# PCB_control_glider_v21.net
KiCad netlist of a schematic drawn in EAGLE
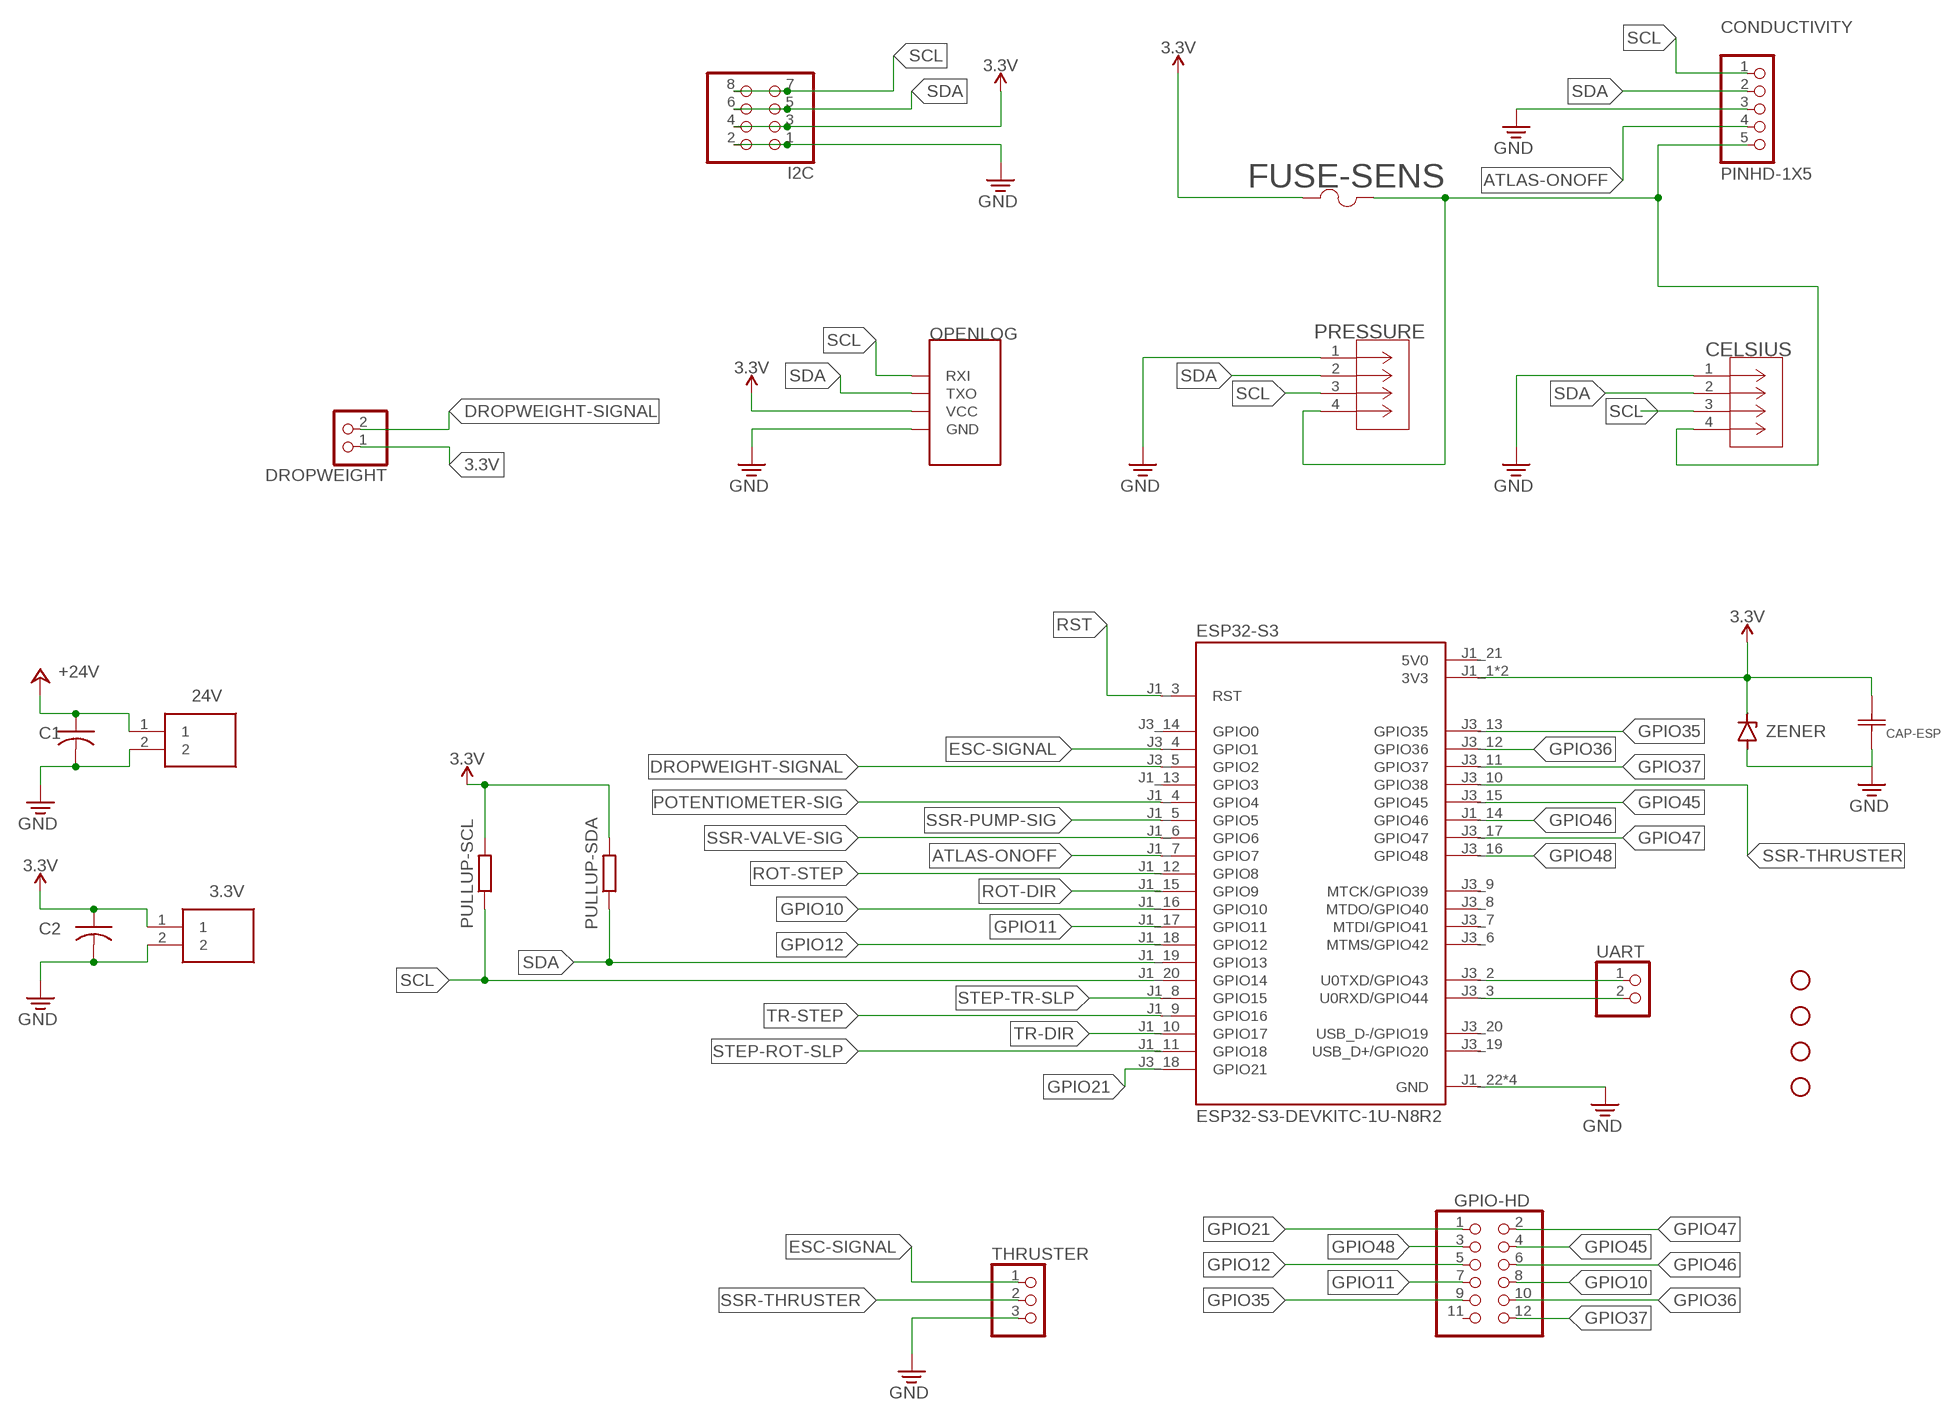
[diagram p0: schematic, sheet 1, part 1 of 2]
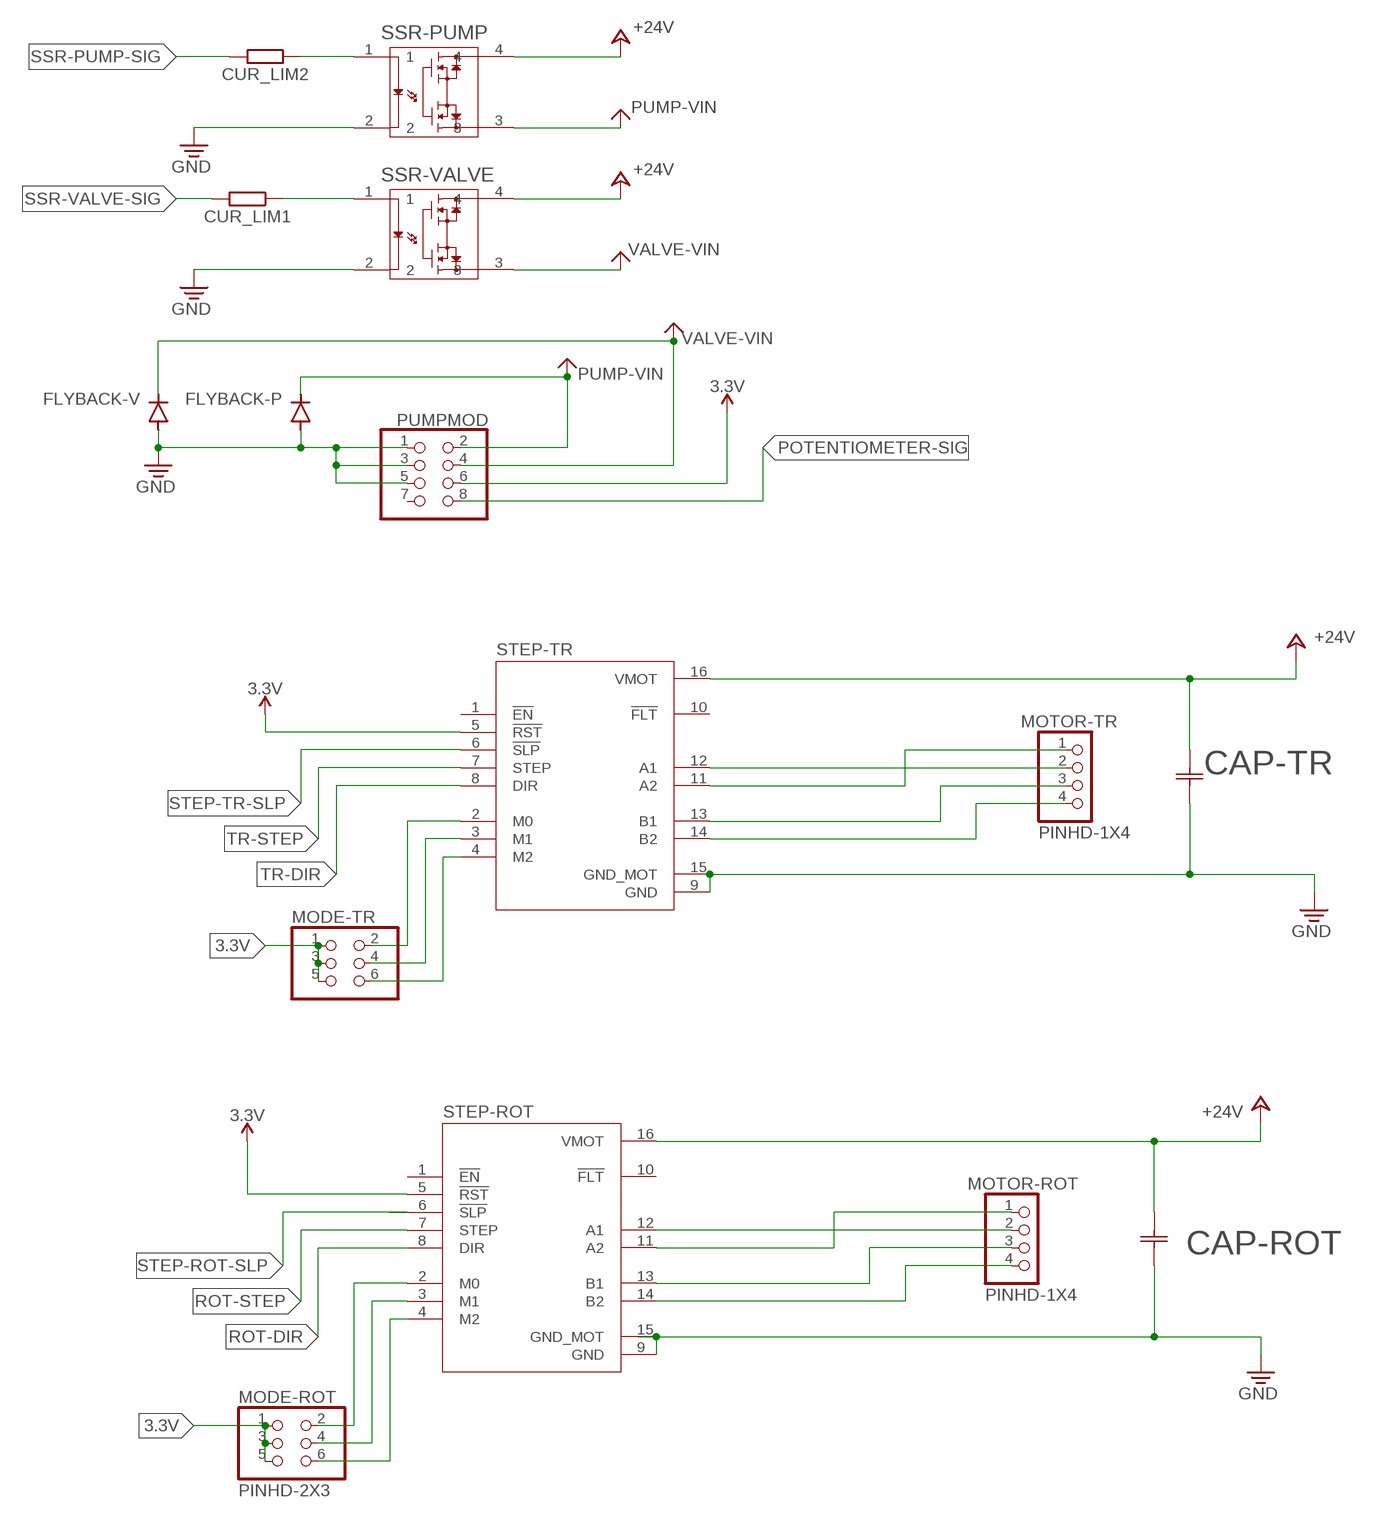
[diagram p1: schematic, sheet 1, part 2 of 2]

(export (version "E")
  (design (tool "Eeschema 10.0.6"))
  (components
    (comp (ref "3.3V")
      (value "CTBP0508_2")
      (footprint "eagle-import:CTBP05082")
      (fields (field (name "MANUFACTURER_PART_NUMBER") "CTBP0508/2"))
      (libsource (lib "eagle-import") (part "CTBP0508_2"))
    )
    (comp (ref "24V")
      (value "CTBP0508_2")
      (footprint "eagle-import:CTBP05082")
      (fields (field (name "MANUFACTURER_PART_NUMBER") "CTBP0508/2"))
      (libsource (lib "eagle-import") (part "CTBP0508_2"))
    )
    (comp (ref "C1")
      (value "ECA-1HM100")
      (footprint "eagle-import:CAP_RADIAL_2MM")
      (fields
        (field (name "DIGIKEY_PART_NUMBER") "P5178-ND")
        (field (name "MANUFACTURER") "Panasonic Electronic Components")
        (field (name "CREATED_BY") "PCBLayout.com")
      )
      (libsource (lib "eagle-import") (part "ECA-1HM100"))
    )
    (comp (ref "C2")
      (value "ECA-1HM100")
      (footprint "eagle-import:CAP_RADIAL_2MM")
      (fields
        (field (name "DIGIKEY_PART_NUMBER") "P5178-ND")
        (field (name "MANUFACTURER") "Panasonic Electronic Components")
        (field (name "CREATED_BY") "PCBLayout.com")
      )
      (libsource (lib "eagle-import") (part "ECA-1HM100"))
    )
    (comp (ref "CAP-ESP")
      (value "EEUHD1H101BCAP_PAN_8X11.5_PAN")
      (footprint "eagle-import:CAP_PAN_8X11.5_PAN")
      (fields
        (field (name "MANUFACTURER_PART_NUMBER") "EEUHD1H101B")
        (field (name "COPYRIGHT") "Copyright (C) 2024 Ultra Librarian. All rights reserved.")
      )
      (libsource (lib "eagle-import") (part "EEUHD1H101BCAP_PAN_8X11.5_PAN"))
    )
    (comp (ref "CAP-ROT")
      (value "EEUHD1H101BCAP_PAN_8X11.5_PAN")
      (footprint "eagle-import:CAP_PAN_8X11.5_PAN")
      (fields
        (field (name "MANUFACTURER_PART_NUMBER") "EEUHD1H101B")
        (field (name "COPYRIGHT") "Copyright (C) 2024 Ultra Librarian. All rights reserved.")
      )
      (libsource (lib "eagle-import") (part "EEUHD1H101BCAP_PAN_8X11.5_PAN"))
    )
    (comp (ref "CAP-TR")
      (value "EEUHD1H101BCAP_PAN_8X11.5_PAN")
      (footprint "eagle-import:CAP_PAN_8X11.5_PAN")
      (fields
        (field (name "MANUFACTURER_PART_NUMBER") "EEUHD1H101B")
        (field (name "COPYRIGHT") "Copyright (C) 2024 Ultra Librarian. All rights reserved.")
      )
      (libsource (lib "eagle-import") (part "EEUHD1H101BCAP_PAN_8X11.5_PAN"))
    )
    (comp (ref "CELSIUS")
      (value "BM04B-GHS-TBTCONN_BM04B-GHS-TBT_JST")
      (footprint "eagle-import:CONN_BM04B-GHS-TBT_JST")
      (fields
        (field (name "MANUFACTURER_PART_NUMBER") "BM04B-GHS-TBT")
        (field (name "COPYRIGHT") "Copyright (C) 2024 Ultra Librarian. All rights reserved.")
      )
      (libsource (lib "eagle-import") (part "BM04B-GHS-TBTCONN_BM04B-GHS-TBT_JST"))
    )
    (comp (ref "CONDUCTIVITY")
      (value "PINHD-1X5")
      (footprint "eagle-import:1X05")
      (fields (field (name "MANUFACTURER") "Generic"))
      (libsource (lib "eagle-import") (part "PINHD-1X5"))
    )
    (comp (ref "CUR_LIM1")
      (value "RESISTOR-BACKUP_AXIAL-10.16MM-PITCH")
      (footprint "eagle-import:RESAD1016W63L850D250B")
      (libsource (lib "eagle-import") (part "RESISTOR-BACKUP_AXIAL-10.16MM-PITCH"))
    )
    (comp (ref "CUR_LIM2")
      (value "RESISTOR-BACKUP_AXIAL-10.16MM-PITCH")
      (footprint "eagle-import:RESAD1016W63L850D250B")
      (libsource (lib "eagle-import") (part "RESISTOR-BACKUP_AXIAL-10.16MM-PITCH"))
    )
    (comp (ref "DROPWEIGHT")
      (value "PINHD-1X2")
      (footprint "eagle-import:1X02")
      (libsource (lib "eagle-import") (part "PINHD-1X2"))
    )
    (comp (ref "ESP32-S3")
      (value "ESP32-S3-DEVKITC-1U-N8R2")
      (footprint "eagle-import:XCVR_ESP32-S3-DEVKITC-1U-N8R2")
      (fields (field (name "MF") "Espressif Systems"))
      (libsource (lib "eagle-import") (part "ESP32-S3-DEVKITC-1U-N8R2"))
    )
    (comp (ref "FLYBACK-P")
      (value "1N4004")
      (footprint "eagle-import:DO-41")
      (fields
        (field (name "DIGIKEY_PART_NUMBER") "1N4004MSCT-ND")
        (field (name "MANUFACTURER") "Micro Commercial Co")
        (field (name "CREATED_BY") "PCBLayout.com")
      )
      (libsource (lib "eagle-import") (part "1N4004"))
    )
    (comp (ref "FLYBACK-V")
      (value "1N4004")
      (footprint "eagle-import:DO-41")
      (fields
        (field (name "DIGIKEY_PART_NUMBER") "1N4004MSCT-ND")
        (field (name "MANUFACTURER") "Micro Commercial Co")
        (field (name "CREATED_BY") "PCBLayout.com")
      )
      (libsource (lib "eagle-import") (part "1N4004"))
    )
    (comp (ref "FUSE-SENS")
      (value "LVR033KFUS_LVR033_TYCO_TYC")
      (footprint "eagle-import:FUS_LVR033_TYCO_TYC")
      (fields
        (field (name "MANUFACTURER_PART_NUMBER") "LVR033K")
        (field (name "COPYRIGHT") "Copyright (C) 2024 Ultra Librarian. All rights reserved.")
      )
      (libsource (lib "eagle-import") (part "LVR033KFUS_LVR033_TYCO_TYC"))
    )
    (comp (ref "GPIO-HD")
      (value "PINHD-2X6")
      (footprint "eagle-import:2X06")
      (fields (field (name "MANUFACTURER") "Generic"))
      (libsource (lib "eagle-import") (part "PINHD-2X6"))
    )
    (comp (ref "H1")
      (value "STAND-OFFTIGHT")
      (footprint "eagle-import:STAND-OFF-TIGHT")
      (libsource (lib "eagle-import") (part "STAND-OFFTIGHT"))
    )
    (comp (ref "H2")
      (value "STAND-OFFTIGHT")
      (footprint "eagle-import:STAND-OFF-TIGHT")
      (libsource (lib "eagle-import") (part "STAND-OFFTIGHT"))
    )
    (comp (ref "H3")
      (value "STAND-OFFTIGHT")
      (footprint "eagle-import:STAND-OFF-TIGHT")
      (libsource (lib "eagle-import") (part "STAND-OFFTIGHT"))
    )
    (comp (ref "H4")
      (value "STAND-OFFTIGHT")
      (footprint "eagle-import:STAND-OFF-TIGHT")
      (libsource (lib "eagle-import") (part "STAND-OFFTIGHT"))
    )
    (comp (ref "I2C")
      (value "PINHD-2X4")
      (footprint "eagle-import:2X04")
      (libsource (lib "eagle-import") (part "PINHD-2X4"))
    )
    (comp (ref "MODE-ROT")
      (value "PINHD-2X3")
      (footprint "eagle-import:2X03")
      (fields (field (name "MANUFACTURER") "Generic"))
      (libsource (lib "eagle-import") (part "PINHD-2X3"))
    )
    (comp (ref "MODE-TR")
      (value "PINHD-2X3")
      (footprint "eagle-import:2X03")
      (fields (field (name "MANUFACTURER") "Generic"))
      (libsource (lib "eagle-import") (part "PINHD-2X3"))
    )
    (comp (ref "MOTOR-ROT")
      (value "PINHD-1X4")
      (footprint "eagle-import:1X04")
      (fields (field (name "MANUFACTURER") "Generic"))
      (libsource (lib "eagle-import") (part "PINHD-1X4"))
    )
    (comp (ref "MOTOR-TR")
      (value "PINHD-1X4")
      (footprint "eagle-import:1X04")
      (fields (field (name "MANUFACTURER") "Generic"))
      (libsource (lib "eagle-import") (part "PINHD-1X4"))
    )
    (comp (ref "PRESSURE")
      (value "BM04B-GHS-TBTCONN_BM04B-GHS-TBT_JST")
      (footprint "eagle-import:CONN_BM04B-GHS-TBT_JST")
      (fields
        (field (name "MANUFACTURER_PART_NUMBER") "BM04B-GHS-TBT")
        (field (name "COPYRIGHT") "Copyright (C) 2024 Ultra Librarian. All rights reserved.")
      )
      (libsource (lib "eagle-import") (part "BM04B-GHS-TBTCONN_BM04B-GHS-TBT_JST"))
    )
    (comp (ref "PULLUP-SCL")
      (value "RESISTOR-BACKUP_AXIAL-10.16MM-PITCH")
      (footprint "eagle-import:RESAD1016W63L850D250B")
      (libsource (lib "eagle-import") (part "RESISTOR-BACKUP_AXIAL-10.16MM-PITCH"))
    )
    (comp (ref "PULLUP-SDA")
      (value "RESISTOR-BACKUP_AXIAL-10.16MM-PITCH")
      (footprint "eagle-import:RESAD1016W63L850D250B")
      (libsource (lib "eagle-import") (part "RESISTOR-BACKUP_AXIAL-10.16MM-PITCH"))
    )
    (comp (ref "PUMPMOD")
      (value "PINHD-2X4")
      (footprint "eagle-import:2X04")
      (libsource (lib "eagle-import") (part "PINHD-2X4"))
    )
    (comp (ref "QWIIC-OPENLOG")
      (value "OPENLOG")
      (footprint "eagle-import:OPENLOG")
      (libsource (lib "eagle-import") (part "OPENLOG"))
    )
    (comp (ref "SSR-PUMP")
      (value "G3VM-61ARA-DIP4_THD_OMR")
      (footprint "eagle-import:A-DIP4_THD_OMR")
      (fields
        (field (name "MANUFACTURER_PART_NUMBER") "G3VM-61AR")
        (field (name "COPYRIGHT") "Copyright (C) 2024 Ultra Librarian. All rights reserved.")
      )
      (libsource (lib "eagle-import") (part "G3VM-61ARA-DIP4_THD_OMR"))
    )
    (comp (ref "SSR-VALVE")
      (value "G3VM-61ARA-DIP4_THD_OMR")
      (footprint "eagle-import:A-DIP4_THD_OMR")
      (fields
        (field (name "MANUFACTURER_PART_NUMBER") "G3VM-61AR")
        (field (name "COPYRIGHT") "Copyright (C) 2024 Ultra Librarian. All rights reserved.")
      )
      (libsource (lib "eagle-import") (part "G3VM-61ARA-DIP4_THD_OMR"))
    )
    (comp (ref "STEP-ROT")
      (value "DRV8825_STEPPER_MOTOR_DRIVER_CARRIER")
      (footprint "eagle-import:IC_DRV8825_STEPPER_MOTOR_DRIVER_CARRIER")
      (fields (field (name "MF") "Pololu") (field (name "MP") "DRV8825 STEPPER MOTOR DRIVER CARRIER"))
      (libsource (lib "eagle-import") (part "DRV8825_STEPPER_MOTOR_DRIVER_CARRIER"))
    )
    (comp (ref "STEP-TR")
      (value "DRV8825_STEPPER_MOTOR_DRIVER_CARRIER")
      (footprint "eagle-import:IC_DRV8825_STEPPER_MOTOR_DRIVER_CARRIER")
      (fields (field (name "MF") "Pololu") (field (name "MP") "DRV8825 STEPPER MOTOR DRIVER CARRIER"))
      (libsource (lib "eagle-import") (part "DRV8825_STEPPER_MOTOR_DRIVER_CARRIER"))
    )
    (comp (ref "THRUSTER")
      (value "PINHD-1X3")
      (footprint "eagle-import:1X03")
      (libsource (lib "eagle-import") (part "PINHD-1X3"))
    )
    (comp (ref "UART")
      (value "PINHD-1X2")
      (footprint "eagle-import:1X02")
      (libsource (lib "eagle-import") (part "PINHD-1X2"))
    )
    (comp (ref "ZENER")
      (value "ZENER_DIODE-AXIAL")
      (footprint "eagle-import:DIODE-AXIAL")
      (libsource (lib "eagle-import") (part "ZENER_DIODE-AXIAL"))
    )
  )
  (nets
    (net (code "1") (name "+24V") (class "Default")
      (node (ref "24V") (pin "1") (pinfunction "1_1") (pintype "bidirectional"))
      (node (ref "C1") (pin "1") (pinfunction "1_1") (pintype "passive"))
      (node (ref "CAP-ROT") (pin "1") (pinfunction "1_1") (pintype "passive"))
      (node (ref "CAP-TR") (pin "1") (pinfunction "1_1") (pintype "passive"))
      (node (ref "SSR-PUMP") (pin "4") (pinfunction "4_4") (pintype "passive"))
      (node (ref "SSR-VALVE") (pin "4") (pinfunction "4_4") (pintype "passive"))
      (node (ref "STEP-ROT") (pin "16") (pinfunction "VMOT_16") (pintype "power_in"))
      (node (ref "STEP-TR") (pin "16") (pinfunction "VMOT_16") (pintype "power_in"))
    )
    (net (code "2") (name "/5V0") (class "Default")
      (node (ref "ESP32-S3") (pin "J1_21") (pinfunction "5V0_J1_21") (pintype "power_in"))
    )
    (net (code "3") (name "3.3V") (class "Default")
      (node (ref "3.3V") (pin "1") (pinfunction "1_1") (pintype "bidirectional"))
      (node (ref "C2") (pin "1") (pinfunction "1_1") (pintype "passive"))
      (node (ref "CAP-ESP") (pin "1") (pinfunction "1_1") (pintype "passive"))
      (node (ref "DROPWEIGHT") (pin "1") (pinfunction "1_1") (pintype "passive"))
      (node (ref "ESP32-S3") (pin "J1_1") (pinfunction "3V3_J1_1") (pintype "power_in"))
      (node (ref "ESP32-S3") (pin "J1_2") (pinfunction "3V3_J1_2") (pintype "power_in"))
      (node (ref "FUSE-SENS") (pin "1") (pinfunction "1_1") (pintype "passive"))
      (node (ref "I2C") (pin "3") (pinfunction "3_3") (pintype "passive"))
      (node (ref "I2C") (pin "4") (pinfunction "4_4") (pintype "passive"))
      (node (ref "MODE-ROT") (pin "1") (pinfunction "1_1") (pintype "passive"))
      (node (ref "MODE-ROT") (pin "3") (pinfunction "3_3") (pintype "passive"))
      (node (ref "MODE-ROT") (pin "5") (pinfunction "5_5") (pintype "passive"))
      (node (ref "MODE-TR") (pin "1") (pinfunction "1_1") (pintype "passive"))
      (node (ref "MODE-TR") (pin "3") (pinfunction "3_3") (pintype "passive"))
      (node (ref "MODE-TR") (pin "5") (pinfunction "5_5") (pintype "passive"))
      (node (ref "PULLUP-SCL") (pin "2") (pinfunction "2_2") (pintype "passive"))
      (node (ref "PULLUP-SDA") (pin "2") (pinfunction "2_2") (pintype "passive"))
      (node (ref "PUMPMOD") (pin "6") (pinfunction "6_6") (pintype "passive"))
      (node (ref "QWIIC-OPENLOG") (pin "VCC") (pinfunction "VCC_VCC") (pintype "power_in"))
      (node (ref "STEP-ROT") (pin "5") (pinfunction "~{RST}_5") (pintype "input"))
      (node (ref "STEP-TR") (pin "5") (pinfunction "~{RST}_5") (pintype "input"))
      (node (ref "ZENER") (pin "2") (pinfunction "C_2") (pintype "passive"))
    )
    (net (code "4") (name "ATLAS-ONOFF") (class "Default")
      (node (ref "CONDUCTIVITY") (pin "4") (pinfunction "4_4") (pintype "passive"))
      (node (ref "ESP32-S3") (pin "J1_7") (pinfunction "GPIO7_J1_7") (pintype "bidirectional"))
    )
    (net (code "5") (name "DROPWEIGHT-SIGNAL") (class "Default")
      (node (ref "DROPWEIGHT") (pin "2") (pinfunction "2_2") (pintype "passive"))
      (node (ref "ESP32-S3") (pin "J3_5") (pinfunction "GPIO2_J3_5") (pintype "bidirectional"))
    )
    (net (code "6") (name "ESC-SIGNAL") (class "Default")
      (node (ref "ESP32-S3") (pin "J3_4") (pinfunction "GPIO1_J3_4") (pintype "bidirectional"))
      (node (ref "THRUSTER") (pin "1") (pinfunction "1_1") (pintype "passive"))
    )
    (net (code "7") (name "GND") (class "Default")
      (node (ref "24V") (pin "2") (pinfunction "2_2") (pintype "bidirectional"))
      (node (ref "3.3V") (pin "2") (pinfunction "2_2") (pintype "bidirectional"))
      (node (ref "C1") (pin "2") (pinfunction "2_2") (pintype "passive"))
      (node (ref "C2") (pin "2") (pinfunction "2_2") (pintype "passive"))
      (node (ref "CAP-ESP") (pin "2") (pinfunction "2_2") (pintype "passive"))
      (node (ref "CAP-ROT") (pin "2") (pinfunction "2_2") (pintype "passive"))
      (node (ref "CAP-TR") (pin "2") (pinfunction "2_2") (pintype "passive"))
      (node (ref "CELSIUS") (pin "1") (pinfunction "1_1") (pintype "passive"))
      (node (ref "CONDUCTIVITY") (pin "3") (pinfunction "3_3") (pintype "passive"))
      (node (ref "ESP32-S3") (pin "J1_22") (pinfunction "GND_J1_22") (pintype "power_in"))
      (node (ref "ESP32-S3") (pin "J3_1") (pinfunction "GND_J3_1") (pintype "power_in"))
      (node (ref "ESP32-S3") (pin "J3_21") (pinfunction "GND_J3_21") (pintype "power_in"))
      (node (ref "ESP32-S3") (pin "J3_22") (pinfunction "GND_J3_22") (pintype "power_in"))
      (node (ref "FLYBACK-P") (pin "A") (pinfunction "A_A") (pintype "passive"))
      (node (ref "FLYBACK-V") (pin "A") (pinfunction "A_A") (pintype "passive"))
      (node (ref "I2C") (pin "1") (pinfunction "1_1") (pintype "passive"))
      (node (ref "I2C") (pin "2") (pinfunction "2_2") (pintype "passive"))
      (node (ref "PRESSURE") (pin "1") (pinfunction "1_1") (pintype "passive"))
      (node (ref "PUMPMOD") (pin "1") (pinfunction "1_1") (pintype "passive"))
      (node (ref "PUMPMOD") (pin "3") (pinfunction "3_3") (pintype "passive"))
      (node (ref "PUMPMOD") (pin "5") (pinfunction "5_5") (pintype "passive"))
      (node (ref "QWIIC-OPENLOG") (pin "GND") (pinfunction "GND_GND") (pintype "power_in"))
      (node (ref "SSR-PUMP") (pin "2") (pinfunction "2_2") (pintype "passive"))
      (node (ref "SSR-VALVE") (pin "2") (pinfunction "2_2") (pintype "passive"))
      (node (ref "STEP-ROT") (pin "15") (pinfunction "GND_MOT_15") (pintype "power_in"))
      (node (ref "STEP-ROT") (pin "9") (pinfunction "GND_9") (pintype "power_in"))
      (node (ref "STEP-TR") (pin "15") (pinfunction "GND_MOT_15") (pintype "power_in"))
      (node (ref "STEP-TR") (pin "9") (pinfunction "GND_9") (pintype "power_in"))
      (node (ref "THRUSTER") (pin "3") (pinfunction "3_3") (pintype "passive"))
      (node (ref "ZENER") (pin "1") (pinfunction "A_1") (pintype "passive"))
    )
    (net (code "8") (name "GPIO10") (class "Default")
      (node (ref "ESP32-S3") (pin "J1_16") (pinfunction "GPIO10_J1_16") (pintype "bidirectional"))
      (node (ref "GPIO-HD") (pin "8") (pinfunction "8_8") (pintype "passive"))
    )
    (net (code "9") (name "GPIO11") (class "Default")
      (node (ref "ESP32-S3") (pin "J1_17") (pinfunction "GPIO11_J1_17") (pintype "bidirectional"))
      (node (ref "GPIO-HD") (pin "7") (pinfunction "7_7") (pintype "passive"))
    )
    (net (code "10") (name "GPIO12") (class "Default")
      (node (ref "ESP32-S3") (pin "J1_18") (pinfunction "GPIO12_J1_18") (pintype "bidirectional"))
      (node (ref "GPIO-HD") (pin "5") (pinfunction "5_5") (pintype "passive"))
    )
    (net (code "11") (name "GPIO21") (class "Default")
      (node (ref "ESP32-S3") (pin "J3_18") (pinfunction "GPIO21_J3_18") (pintype "bidirectional"))
      (node (ref "GPIO-HD") (pin "1") (pinfunction "1_1") (pintype "passive"))
    )
    (net (code "12") (name "GPIO35") (class "Default")
      (node (ref "ESP32-S3") (pin "J3_13") (pinfunction "GPIO35_J3_13") (pintype "bidirectional"))
      (node (ref "GPIO-HD") (pin "9") (pinfunction "9_9") (pintype "passive"))
    )
    (net (code "13") (name "GPIO36") (class "Default")
      (node (ref "ESP32-S3") (pin "J3_12") (pinfunction "GPIO36_J3_12") (pintype "bidirectional"))
      (node (ref "GPIO-HD") (pin "10") (pinfunction "10_10") (pintype "passive"))
    )
    (net (code "14") (name "GPIO37") (class "Default")
      (node (ref "ESP32-S3") (pin "J3_11") (pinfunction "GPIO37_J3_11") (pintype "bidirectional"))
      (node (ref "GPIO-HD") (pin "12") (pinfunction "12_12") (pintype "passive"))
    )
    (net (code "15") (name "GPIO45") (class "Default")
      (node (ref "ESP32-S3") (pin "J3_15") (pinfunction "GPIO45_J3_15") (pintype "bidirectional"))
      (node (ref "GPIO-HD") (pin "4") (pinfunction "4_4") (pintype "passive"))
    )
    (net (code "16") (name "GPIO46") (class "Default")
      (node (ref "ESP32-S3") (pin "J1_14") (pinfunction "GPIO46_J1_14") (pintype "bidirectional"))
      (node (ref "GPIO-HD") (pin "6") (pinfunction "6_6") (pintype "passive"))
    )
    (net (code "17") (name "GPIO47") (class "Default")
      (node (ref "ESP32-S3") (pin "J3_17") (pinfunction "GPIO47_J3_17") (pintype "bidirectional"))
      (node (ref "GPIO-HD") (pin "2") (pinfunction "2_2") (pintype "passive"))
    )
    (net (code "18") (name "GPIO48") (class "Default")
      (node (ref "ESP32-S3") (pin "J3_16") (pinfunction "GPIO48_J3_16") (pintype "bidirectional"))
      (node (ref "GPIO-HD") (pin "3") (pinfunction "3_3") (pintype "passive"))
    )
    (net (code "19") (name "Net-(CELSIUS-Pad4)") (class "Default")
      (node (ref "CELSIUS") (pin "4") (pinfunction "4_4") (pintype "passive"))
      (node (ref "CONDUCTIVITY") (pin "5") (pinfunction "5_5") (pintype "passive"))
      (node (ref "FUSE-SENS") (pin "2") (pinfunction "2_2") (pintype "passive"))
      (node (ref "PRESSURE") (pin "4") (pinfunction "4_4") (pintype "passive"))
    )
    (net (code "20") (name "Net-(CUR_LIM1-Pad1)") (class "Default")
      (node (ref "CUR_LIM1") (pin "1") (pinfunction "1_1") (pintype "passive"))
      (node (ref "SSR-VALVE") (pin "1") (pinfunction "1_1") (pintype "passive"))
    )
    (net (code "21") (name "Net-(CUR_LIM2-Pad1)") (class "Default")
      (node (ref "CUR_LIM2") (pin "1") (pinfunction "1_1") (pintype "passive"))
      (node (ref "SSR-PUMP") (pin "1") (pinfunction "1_1") (pintype "passive"))
    )
    (net (code "22") (name "Net-(ESP32-S3-U0RXD{slash}GPIO44)") (class "Default")
      (node (ref "ESP32-S3") (pin "J3_3") (pinfunction "U0RXD/GPIO44_J3_3") (pintype "bidirectional"))
      (node (ref "UART") (pin "2") (pinfunction "2_2") (pintype "passive"))
    )
    (net (code "23") (name "Net-(ESP32-S3-U0TXD{slash}GPIO43)") (class "Default")
      (node (ref "ESP32-S3") (pin "J3_2") (pinfunction "U0TXD/GPIO43_J3_2") (pintype "bidirectional"))
      (node (ref "UART") (pin "1") (pinfunction "1_1") (pintype "passive"))
    )
    (net (code "24") (name "Net-(STEP-ROT-A1)") (class "Default")
      (node (ref "MOTOR-ROT") (pin "2") (pinfunction "2_2") (pintype "passive"))
      (node (ref "STEP-ROT") (pin "12") (pinfunction "A1_12") (pintype "output"))
    )
    (net (code "25") (name "Net-(STEP-ROT-A2)") (class "Default")
      (node (ref "MOTOR-ROT") (pin "1") (pinfunction "1_1") (pintype "passive"))
      (node (ref "STEP-ROT") (pin "11") (pinfunction "A2_11") (pintype "output"))
    )
    (net (code "26") (name "Net-(STEP-ROT-B1)") (class "Default")
      (node (ref "MOTOR-ROT") (pin "3") (pinfunction "3_3") (pintype "passive"))
      (node (ref "STEP-ROT") (pin "13") (pinfunction "B1_13") (pintype "output"))
    )
    (net (code "27") (name "Net-(STEP-ROT-B2)") (class "Default")
      (node (ref "MOTOR-ROT") (pin "4") (pinfunction "4_4") (pintype "passive"))
      (node (ref "STEP-ROT") (pin "14") (pinfunction "B2_14") (pintype "output"))
    )
    (net (code "28") (name "Net-(STEP-ROT-M0)") (class "Default")
      (node (ref "MODE-ROT") (pin "2") (pinfunction "2_2") (pintype "passive"))
      (node (ref "STEP-ROT") (pin "2") (pinfunction "M0_2") (pintype "input"))
    )
    (net (code "29") (name "Net-(STEP-ROT-M1)") (class "Default")
      (node (ref "MODE-ROT") (pin "4") (pinfunction "4_4") (pintype "passive"))
      (node (ref "STEP-ROT") (pin "3") (pinfunction "M1_3") (pintype "input"))
    )
    (net (code "30") (name "Net-(STEP-ROT-M2)") (class "Default")
      (node (ref "MODE-ROT") (pin "6") (pinfunction "6_6") (pintype "passive"))
      (node (ref "STEP-ROT") (pin "4") (pinfunction "M2_4") (pintype "input"))
    )
    (net (code "31") (name "Net-(STEP-TR-A1)") (class "Default")
      (node (ref "MOTOR-TR") (pin "2") (pinfunction "2_2") (pintype "passive"))
      (node (ref "STEP-TR") (pin "12") (pinfunction "A1_12") (pintype "output"))
    )
    (net (code "32") (name "Net-(STEP-TR-A2)") (class "Default")
      (node (ref "MOTOR-TR") (pin "1") (pinfunction "1_1") (pintype "passive"))
      (node (ref "STEP-TR") (pin "11") (pinfunction "A2_11") (pintype "output"))
    )
    (net (code "33") (name "Net-(STEP-TR-B1)") (class "Default")
      (node (ref "MOTOR-TR") (pin "3") (pinfunction "3_3") (pintype "passive"))
      (node (ref "STEP-TR") (pin "13") (pinfunction "B1_13") (pintype "output"))
    )
    (net (code "34") (name "Net-(STEP-TR-B2)") (class "Default")
      (node (ref "MOTOR-TR") (pin "4") (pinfunction "4_4") (pintype "passive"))
      (node (ref "STEP-TR") (pin "14") (pinfunction "B2_14") (pintype "output"))
    )
    (net (code "35") (name "Net-(STEP-TR-M0)") (class "Default")
      (node (ref "MODE-TR") (pin "2") (pinfunction "2_2") (pintype "passive"))
      (node (ref "STEP-TR") (pin "2") (pinfunction "M0_2") (pintype "input"))
    )
    (net (code "36") (name "Net-(STEP-TR-M1)") (class "Default")
      (node (ref "MODE-TR") (pin "4") (pinfunction "4_4") (pintype "passive"))
      (node (ref "STEP-TR") (pin "3") (pinfunction "M1_3") (pintype "input"))
    )
    (net (code "37") (name "Net-(STEP-TR-M2)") (class "Default")
      (node (ref "MODE-TR") (pin "6") (pinfunction "6_6") (pintype "passive"))
      (node (ref "STEP-TR") (pin "4") (pinfunction "M2_4") (pintype "input"))
    )
    (net (code "38") (name "POTENTIOMETER-SIG") (class "Default")
      (node (ref "ESP32-S3") (pin "J1_4") (pinfunction "GPIO4_J1_4") (pintype "bidirectional"))
      (node (ref "PUMPMOD") (pin "8") (pinfunction "8_8") (pintype "passive"))
    )
    (net (code "39") (name "PUMP-VIN") (class "Default")
      (node (ref "FLYBACK-P") (pin "C") (pinfunction "C_C") (pintype "passive"))
      (node (ref "PUMPMOD") (pin "2") (pinfunction "2_2") (pintype "passive"))
      (node (ref "SSR-PUMP") (pin "3") (pinfunction "3_3") (pintype "passive"))
    )
    (net (code "40") (name "ROT-DIR") (class "Default")
      (node (ref "ESP32-S3") (pin "J1_15") (pinfunction "GPIO9_J1_15") (pintype "bidirectional"))
      (node (ref "STEP-ROT") (pin "8") (pinfunction "DIR_8") (pintype "input"))
    )
    (net (code "41") (name "ROT-STEP") (class "Default")
      (node (ref "ESP32-S3") (pin "J1_12") (pinfunction "GPIO8_J1_12") (pintype "bidirectional"))
      (node (ref "STEP-ROT") (pin "7") (pinfunction "STEP_7") (pintype "input"))
    )
    (net (code "42") (name "RST") (class "Default")
      (node (ref "ESP32-S3") (pin "J1_3") (pinfunction "RST_J1_3") (pintype "input"))
    )
    (net (code "43") (name "SCL") (class "Default")
      (node (ref "CELSIUS") (pin "3") (pinfunction "3_3") (pintype "passive"))
      (node (ref "CONDUCTIVITY") (pin "1") (pinfunction "1_1") (pintype "passive"))
      (node (ref "ESP32-S3") (pin "J1_20") (pinfunction "GPIO14_J1_20") (pintype "bidirectional"))
      (node (ref "I2C") (pin "7") (pinfunction "7_7") (pintype "passive"))
      (node (ref "I2C") (pin "8") (pinfunction "8_8") (pintype "passive"))
      (node (ref "PRESSURE") (pin "3") (pinfunction "3_3") (pintype "passive"))
      (node (ref "PULLUP-SCL") (pin "1") (pinfunction "1_1") (pintype "passive"))
      (node (ref "QWIIC-OPENLOG") (pin "RXI") (pinfunction "RXI_RXI") (pintype "input"))
    )
    (net (code "44") (name "SDA") (class "Default")
      (node (ref "CELSIUS") (pin "2") (pinfunction "2_2") (pintype "passive"))
      (node (ref "CONDUCTIVITY") (pin "2") (pinfunction "2_2") (pintype "passive"))
      (node (ref "ESP32-S3") (pin "J1_19") (pinfunction "GPIO13_J1_19") (pintype "bidirectional"))
      (node (ref "I2C") (pin "5") (pinfunction "5_5") (pintype "passive"))
      (node (ref "I2C") (pin "6") (pinfunction "6_6") (pintype "passive"))
      (node (ref "PRESSURE") (pin "2") (pinfunction "2_2") (pintype "passive"))
      (node (ref "PULLUP-SDA") (pin "1") (pinfunction "1_1") (pintype "passive"))
      (node (ref "QWIIC-OPENLOG") (pin "TXO") (pinfunction "TXO_TXO") (pintype "output"))
    )
    (net (code "45") (name "SSR-PUMP-SIG") (class "Default")
      (node (ref "CUR_LIM2") (pin "2") (pinfunction "2_2") (pintype "passive"))
      (node (ref "ESP32-S3") (pin "J1_5") (pinfunction "GPIO5_J1_5") (pintype "bidirectional"))
    )
    (net (code "46") (name "SSR-THRUSTER") (class "Default")
      (node (ref "ESP32-S3") (pin "J3_10") (pinfunction "GPIO38_J3_10") (pintype "bidirectional"))
      (node (ref "THRUSTER") (pin "2") (pinfunction "2_2") (pintype "passive"))
    )
    (net (code "47") (name "SSR-VALVE-SIG") (class "Default")
      (node (ref "CUR_LIM1") (pin "2") (pinfunction "2_2") (pintype "passive"))
      (node (ref "ESP32-S3") (pin "J1_6") (pinfunction "GPIO6_J1_6") (pintype "bidirectional"))
    )
    (net (code "48") (name "STEP-ROT-SLP") (class "Default")
      (node (ref "ESP32-S3") (pin "J1_11") (pinfunction "GPIO18_J1_11") (pintype "bidirectional"))
      (node (ref "STEP-ROT") (pin "6") (pinfunction "~{SLP}_6") (pintype "input"))
    )
    (net (code "49") (name "STEP-TR-SLP") (class "Default")
      (node (ref "ESP32-S3") (pin "J1_8") (pinfunction "GPIO15_J1_8") (pintype "bidirectional"))
      (node (ref "STEP-TR") (pin "6") (pinfunction "~{SLP}_6") (pintype "input"))
    )
    (net (code "50") (name "TR-DIR") (class "Default")
      (node (ref "ESP32-S3") (pin "J1_10") (pinfunction "GPIO17_J1_10") (pintype "bidirectional"))
      (node (ref "STEP-TR") (pin "8") (pinfunction "DIR_8") (pintype "input"))
    )
    (net (code "51") (name "TR-STEP") (class "Default")
      (node (ref "ESP32-S3") (pin "J1_9") (pinfunction "GPIO16_J1_9") (pintype "bidirectional"))
      (node (ref "STEP-TR") (pin "7") (pinfunction "STEP_7") (pintype "input"))
    )
    (net (code "52") (name "VALVE-VIN") (class "Default")
      (node (ref "FLYBACK-V") (pin "C") (pinfunction "C_C") (pintype "passive"))
      (node (ref "PUMPMOD") (pin "4") (pinfunction "4_4") (pintype "passive"))
      (node (ref "SSR-VALVE") (pin "3") (pinfunction "3_3") (pintype "passive"))
    )
    (net (code "53") (name "unconnected-(ESP32-S3-GPIO0-PadJ3_14)") (class "Default")
      (node (ref "ESP32-S3") (pin "J3_14") (pinfunction "GPIO0_J3_14") (pintype "bidirectional"))
    )
    (net (code "54") (name "unconnected-(ESP32-S3-GPIO3-PadJ1_13)") (class "Default")
      (node (ref "ESP32-S3") (pin "J1_13") (pinfunction "GPIO3_J1_13") (pintype "bidirectional"))
    )
    (net (code "55") (name "unconnected-(ESP32-S3-MTCK{slash}GPIO39-PadJ3_9)") (class "Default")
      (node (ref "ESP32-S3") (pin "J3_9") (pinfunction "MTCK/GPIO39_J3_9") (pintype "bidirectional"))
    )
    (net (code "56") (name "unconnected-(ESP32-S3-MTDI{slash}GPIO41-PadJ3_7)") (class "Default")
      (node (ref "ESP32-S3") (pin "J3_7") (pinfunction "MTDI/GPIO41_J3_7") (pintype "bidirectional"))
    )
    (net (code "57") (name "unconnected-(ESP32-S3-MTDO{slash}GPIO40-PadJ3_8)") (class "Default")
      (node (ref "ESP32-S3") (pin "J3_8") (pinfunction "MTDO/GPIO40_J3_8") (pintype "bidirectional"))
    )
    (net (code "58") (name "unconnected-(ESP32-S3-MTMS{slash}GPIO42-PadJ3_6)") (class "Default")
      (node (ref "ESP32-S3") (pin "J3_6") (pinfunction "MTMS/GPIO42_J3_6") (pintype "bidirectional"))
    )
    (net (code "59") (name "unconnected-(ESP32-S3-USB_D+{slash}GPIO20-PadJ3_19)") (class "Default")
      (node (ref "ESP32-S3") (pin "J3_19") (pinfunction "USB_D+/GPIO20_J3_19") (pintype "bidirectional"))
    )
    (net (code "60") (name "unconnected-(ESP32-S3-USB_D-{slash}GPIO19-PadJ3_20)") (class "Default")
      (node (ref "ESP32-S3") (pin "J3_20") (pinfunction "USB_D-/GPIO19_J3_20") (pintype "bidirectional"))
    )
    (net (code "61") (name "unconnected-(GPIO-HD-Pad11)") (class "Default")
      (node (ref "GPIO-HD") (pin "11") (pinfunction "11_11") (pintype "passive"))
    )
    (net (code "62") (name "unconnected-(PUMPMOD-Pad7)") (class "Default")
      (node (ref "PUMPMOD") (pin "7") (pinfunction "7_7") (pintype "passive"))
    )
    (net (code "63") (name "unconnected-(STEP-ROT-~{EN}-Pad1)") (class "Default")
      (node (ref "STEP-ROT") (pin "1") (pinfunction "~{EN}_1") (pintype "input"))
    )
    (net (code "64") (name "unconnected-(STEP-ROT-~{FLT}-Pad10)") (class "Default")
      (node (ref "STEP-ROT") (pin "10") (pinfunction "~{FLT}_10") (pintype "output"))
    )
    (net (code "65") (name "unconnected-(STEP-TR-~{EN}-Pad1)") (class "Default")
      (node (ref "STEP-TR") (pin "1") (pinfunction "~{EN}_1") (pintype "input"))
    )
    (net (code "66") (name "unconnected-(STEP-TR-~{FLT}-Pad10)") (class "Default")
      (node (ref "STEP-TR") (pin "10") (pinfunction "~{FLT}_10") (pintype "output"))
    )
  )
)
